# ultrasonic_distance_meter.net
KiCad netlist of a schematic drawn in EAGLE
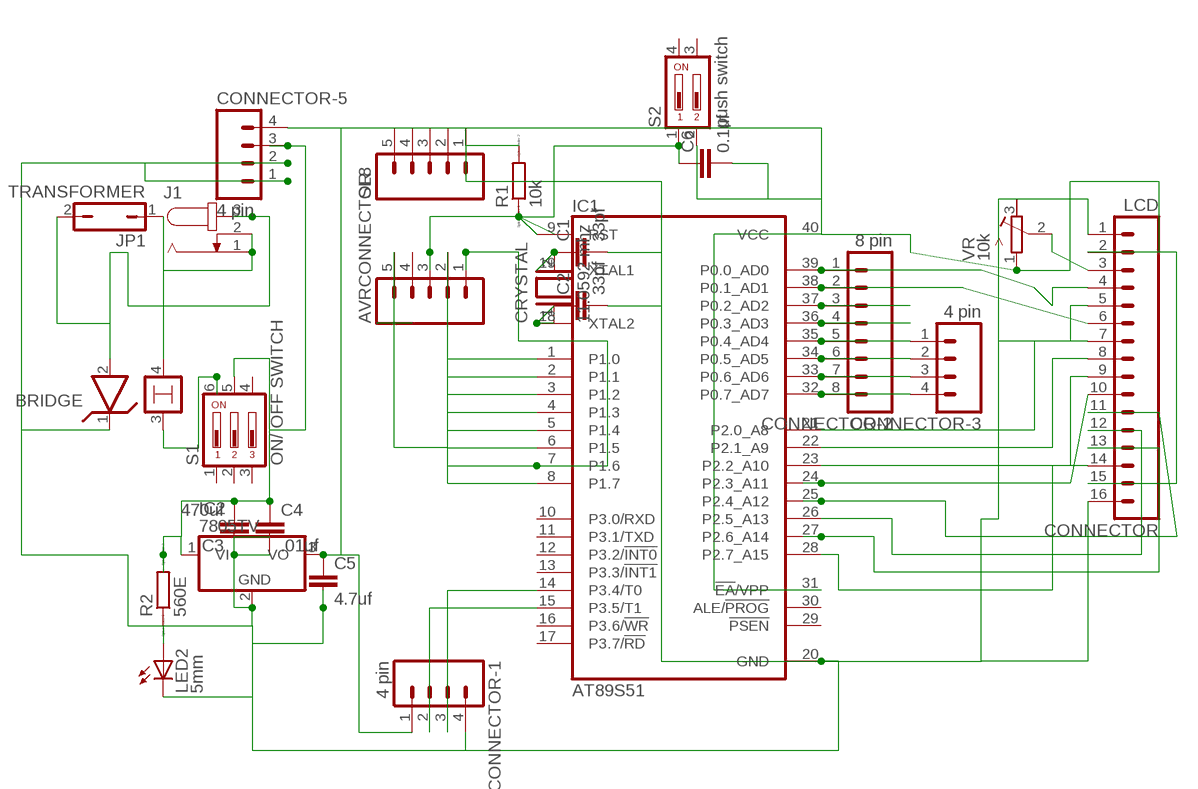
[diagram p0: schematic, sheet 1]

(export (version "E")
  (design (tool "Eeschema 10.0.6"))
  (components
    (comp (ref "AVRCONNECTOR")
      (value "M05")
      (footprint "eagle-import:05P")
      (libsource (lib "eagle-import") (part "M05"))
    )
    (comp (ref "BRIDGE")
      (value "LM399H")
      (footprint "eagle-import:TO39_4")
      (libsource (lib "eagle-import") (part "LM399H"))
    )
    (comp (ref "C1")
      (value "33pf")
      (footprint "eagle-import:C025-024X044")
      (libsource (lib "eagle-import") (part "C-EU025-024X044"))
    )
    (comp (ref "C2")
      (value "33pf")
      (footprint "eagle-import:C025-024X044")
      (libsource (lib "eagle-import") (part "C-EU025-024X044"))
    )
    (comp (ref "C3")
      (value "470uf")
      (footprint "eagle-import:C5B7.2")
      (libsource (lib "eagle-import") (part "C5/7.2"))
    )
    (comp (ref "C4")
      (value ".01uf")
      (footprint "eagle-import:C2.5-3")
      (libsource (lib "eagle-import") (part "C2,5-3"))
    )
    (comp (ref "C5")
      (value "4.7uf")
      (footprint "eagle-import:C2.5-3")
      (libsource (lib "eagle-import") (part "C2,5-3"))
    )
    (comp (ref "C6")
      (value "0.1uf")
      (footprint "eagle-import:C2.5-6")
      (libsource (lib "eagle-import") (part "C2.5/6"))
    )
    (comp (ref "CONNECTOR")
      (value "LCD")
      (footprint "eagle-import:16P")
      (libsource (lib "eagle-import") (part "M16"))
    )
    (comp (ref "CONNECTOR-1")
      (value "4 pin")
      (footprint "eagle-import:04P")
      (fields (field (name "OC_FARNELL") "unknown") (field (name "OC_NEWARK") "unknown"))
      (libsource (lib "eagle-import") (part "M04"))
    )
    (comp (ref "CONNECTOR-2")
      (value "8 pin")
      (footprint "eagle-import:08P")
      (libsource (lib "eagle-import") (part "M08"))
    )
    (comp (ref "CONNECTOR-3")
      (value "4 pin")
      (footprint "eagle-import:04P")
      (fields (field (name "OC_FARNELL") "unknown") (field (name "OC_NEWARK") "unknown"))
      (libsource (lib "eagle-import") (part "M04"))
    )
    (comp (ref "CONNECTOR-5")
      (value "4 pin")
      (footprint "eagle-import:04P")
      (libsource (lib "eagle-import") (part "M04"))
    )
    (comp (ref "CRYSTAL")
      (value "11.0592 mhz")
      (footprint "eagle-import:QS")
      (libsource (lib "eagle-import") (part "XTAL/S"))
    )
    (comp (ref "IC1")
      (value "AT89S51")
      (footprint "eagle-import:DIL40")
      (libsource (lib "eagle-import") (part "AT89C51-PC12"))
    )
    (comp (ref "IC2")
      (value "7805TV")
      (footprint "eagle-import:TO220V")
      (libsource (lib "eagle-import") (part "78TV05"))
    )
    (comp (ref "J1")
      (value "JACK-PLUG0")
      (footprint "eagle-import:SPC4077")
      (libsource (lib "eagle-import") (part "JACK-PLUG0"))
    )
    (comp (ref "JP1")
      (value "TRANSFORMER")
      (footprint "eagle-import:JP1")
      (libsource (lib "eagle-import") (part "JP1Q"))
    )
    (comp (ref "LED2")
      (value "5mm")
      (footprint "eagle-import:LED5MM")
      (libsource (lib "eagle-import") (part "LED5MM"))
    )
    (comp (ref "R1")
      (value "10k")
      (footprint "eagle-import:0204_7")
      (libsource (lib "eagle-import") (part "R0204/7"))
    )
    (comp (ref "R2")
      (value "560E")
      (footprint "eagle-import:0204_7")
      (libsource (lib "eagle-import") (part "R0204/7"))
    )
    (comp (ref "S1")
      (value "ON/ OFF SWITCH")
      (footprint "eagle-import:DA-03")
      (fields (field (name "MPN") "MCDA03"))
      (libsource (lib "eagle-import") (part "DA03"))
    )
    (comp (ref "S2")
      (value "push switch")
      (footprint "eagle-import:DP-02")
      (fields (field (name "MPN") "MCDP02"))
      (libsource (lib "eagle-import") (part "DP02"))
    )
    (comp (ref "SL8")
      (value "M05")
      (footprint "eagle-import:05P")
      (libsource (lib "eagle-import") (part "M05"))
    )
    (comp (ref "VR")
      (value "10k")
      (footprint "eagle-import:RTRIM64P")
      (libsource (lib "eagle-import") (part "R-TRIMM64P"))
    )
  )
  (nets
    (net (code "1") (name "/N$39") (class "Default")
      (node (ref "C5") (pin "1") (pinfunction "1_1") (pintype "passive"))
      (node (ref "C6") (pin "2") (pinfunction "2_2") (pintype "passive"))
      (node (ref "CONNECTOR") (pin "15") (pinfunction "15_15") (pintype "passive"))
      (node (ref "CONNECTOR") (pin "2") (pinfunction "2_2") (pintype "passive"))
      (node (ref "CONNECTOR-1") (pin "1") (pinfunction "1_1") (pintype "passive"))
      (node (ref "CONNECTOR-5") (pin "4") (pinfunction "4_4") (pintype "passive"))
      (node (ref "IC1") (pin "31") (pinfunction "~{EA}/VPP_31") (pintype "input"))
      (node (ref "IC1") (pin "40") (pinfunction "VCC_40") (pintype "power_in"))
      (node (ref "IC2") (pin "3") (pinfunction "VO_3") (pintype "passive"))
      (node (ref "S2") (pin "2") (pinfunction "2_2") (pintype "passive"))
      (node (ref "VR") (pin "1") (pinfunction "E_1") (pintype "passive"))
    )
    (net (code "2") (name "Net-(BRIDGE-Pad2)") (class "Default")
      (node (ref "BRIDGE") (pin "2") (pinfunction "2_2") (pintype "input"))
      (node (ref "J1") (pin "3") (pinfunction "3_3") (pintype "passive"))
      (node (ref "JP1") (pin "2") (pinfunction "2_2") (pintype "passive"))
    )
    (net (code "3") (name "Net-(BRIDGE-Pad3)") (class "Default")
      (node (ref "BRIDGE") (pin "3") (pinfunction "3_3") (pintype "input"))
      (node (ref "S1") (pin "6") (pinfunction "6_6") (pintype "passive"))
    )
    (net (code "4") (name "Net-(BRIDGE-Pad4)") (class "Default")
      (node (ref "BRIDGE") (pin "4") (pinfunction "4_4") (pintype "input"))
      (node (ref "J1") (pin "1") (pinfunction "1_1") (pintype "passive"))
      (node (ref "J1") (pin "2") (pinfunction "2_2") (pintype "passive"))
      (node (ref "JP1") (pin "1") (pinfunction "1_1") (pintype "passive"))
    )
    (net (code "5") (name "Net-(IC1-GND)") (class "Default")
      (node (ref "BRIDGE") (pin "1") (pinfunction "1_1") (pintype "input"))
      (node (ref "C1") (pin "2") (pinfunction "2_2") (pintype "passive"))
      (node (ref "C2") (pin "2") (pinfunction "2_2") (pintype "passive"))
      (node (ref "C3") (pin "1") (pinfunction "1_1") (pintype "passive"))
      (node (ref "C4") (pin "2") (pinfunction "2_2") (pintype "passive"))
      (node (ref "C5") (pin "2") (pinfunction "2_2") (pintype "passive"))
      (node (ref "CONNECTOR") (pin "1") (pinfunction "1_1") (pintype "passive"))
      (node (ref "CONNECTOR") (pin "16") (pinfunction "16_16") (pintype "passive"))
      (node (ref "CONNECTOR") (pin "5") (pinfunction "5_5") (pintype "passive"))
      (node (ref "CONNECTOR-1") (pin "4") (pinfunction "4_4") (pintype "passive"))
      (node (ref "CONNECTOR-5") (pin "1") (pinfunction "1_1") (pintype "passive"))
      (node (ref "CONNECTOR-5") (pin "2") (pinfunction "2_2") (pintype "passive"))
      (node (ref "IC1") (pin "20") (pinfunction "GND_20") (pintype "power_in"))
      (node (ref "IC2") (pin "2") (pinfunction "GND_2") (pintype "passive"))
      (node (ref "LED2") (pin "K") (pinfunction "C_K") (pintype "passive"))
      (node (ref "R1") (pin "2") (pinfunction "2_2") (pintype "passive"))
      (node (ref "SL8") (pin "1") (pinfunction "1_1") (pintype "passive"))
      (node (ref "VR") (pin "3") (pinfunction "A_3") (pintype "passive"))
    )
    (net (code "6") (name "Net-(IC1-P0.0_AD0)") (class "Default")
      (node (ref "CONNECTOR") (pin "4") (pinfunction "4_4") (pintype "passive"))
      (node (ref "CONNECTOR-2") (pin "1") (pinfunction "1_1") (pintype "passive"))
      (node (ref "IC1") (pin "39") (pinfunction "P0.0_AD0_39") (pintype "bidirectional"))
    )
    (net (code "7") (name "Net-(IC1-P0.1_AD1)") (class "Default")
      (node (ref "CONNECTOR") (pin "6") (pinfunction "6_6") (pintype "passive"))
      (node (ref "CONNECTOR-2") (pin "2") (pinfunction "2_2") (pintype "passive"))
      (node (ref "IC1") (pin "38") (pinfunction "P0.1_AD1_38") (pintype "bidirectional"))
    )
    (net (code "8") (name "Net-(IC1-P0.2_AD2)") (class "Default")
      (node (ref "CONNECTOR-2") (pin "3") (pinfunction "3_3") (pintype "passive"))
      (node (ref "IC1") (pin "37") (pinfunction "P0.2_AD2_37") (pintype "bidirectional"))
    )
    (net (code "9") (name "Net-(IC1-P0.3_AD3)") (class "Default")
      (node (ref "CONNECTOR-2") (pin "4") (pinfunction "4_4") (pintype "passive"))
      (node (ref "IC1") (pin "36") (pinfunction "P0.3_AD3_36") (pintype "bidirectional"))
    )
    (net (code "10") (name "Net-(IC1-P0.4_AD4)") (class "Default")
      (node (ref "CONNECTOR-2") (pin "5") (pinfunction "5_5") (pintype "passive"))
      (node (ref "CONNECTOR-3") (pin "1") (pinfunction "1_1") (pintype "passive"))
      (node (ref "IC1") (pin "35") (pinfunction "P0.4_AD4_35") (pintype "bidirectional"))
    )
    (net (code "11") (name "Net-(IC1-P0.5_AD5)") (class "Default")
      (node (ref "CONNECTOR-2") (pin "6") (pinfunction "6_6") (pintype "passive"))
      (node (ref "CONNECTOR-3") (pin "2") (pinfunction "2_2") (pintype "passive"))
      (node (ref "IC1") (pin "34") (pinfunction "P0.5_AD5_34") (pintype "bidirectional"))
    )
    (net (code "12") (name "Net-(IC1-P0.6_AD6)") (class "Default")
      (node (ref "CONNECTOR-2") (pin "7") (pinfunction "7_7") (pintype "passive"))
      (node (ref "CONNECTOR-3") (pin "3") (pinfunction "3_3") (pintype "passive"))
      (node (ref "IC1") (pin "33") (pinfunction "P0.6_AD6_33") (pintype "bidirectional"))
    )
    (net (code "13") (name "Net-(IC1-P0.7_AD7)") (class "Default")
      (node (ref "CONNECTOR-2") (pin "8") (pinfunction "8_8") (pintype "passive"))
      (node (ref "CONNECTOR-3") (pin "4") (pinfunction "4_4") (pintype "passive"))
      (node (ref "IC1") (pin "32") (pinfunction "P0.7_AD7_32") (pintype "bidirectional"))
    )
    (net (code "14") (name "Net-(IC1-P1.5)") (class "Default")
      (node (ref "AVRCONNECTOR") (pin "5") (pinfunction "5_5") (pintype "passive"))
      (node (ref "IC1") (pin "6") (pinfunction "P1.5_6") (pintype "bidirectional"))
    )
    (net (code "15") (name "Net-(IC1-P1.6)") (class "Default")
      (node (ref "AVRCONNECTOR") (pin "1") (pinfunction "1_1") (pintype "passive"))
      (node (ref "IC1") (pin "7") (pinfunction "P1.6_7") (pintype "bidirectional"))
    )
    (net (code "16") (name "Net-(IC1-P1.7)") (class "Default")
      (node (ref "AVRCONNECTOR") (pin "2") (pinfunction "2_2") (pintype "passive"))
      (node (ref "IC1") (pin "8") (pinfunction "P1.7_8") (pintype "bidirectional"))
    )
    (net (code "17") (name "Net-(IC1-P2.0_A8)") (class "Default")
      (node (ref "CONNECTOR") (pin "7") (pinfunction "7_7") (pintype "passive"))
      (node (ref "IC1") (pin "21") (pinfunction "P2.0_A8_21") (pintype "bidirectional"))
    )
    (net (code "18") (name "Net-(IC1-P2.1_A9)") (class "Default")
      (node (ref "CONNECTOR") (pin "8") (pinfunction "8_8") (pintype "passive"))
      (node (ref "IC1") (pin "22") (pinfunction "P2.1_A9_22") (pintype "bidirectional"))
    )
    (net (code "19") (name "Net-(IC1-P2.2_A10)") (class "Default")
      (node (ref "CONNECTOR") (pin "9") (pinfunction "9_9") (pintype "passive"))
      (node (ref "IC1") (pin "23") (pinfunction "P2.2_A10_23") (pintype "bidirectional"))
    )
    (net (code "20") (name "Net-(IC1-P2.3_A11)") (class "Default")
      (node (ref "CONNECTOR") (pin "10") (pinfunction "10_10") (pintype "passive"))
      (node (ref "IC1") (pin "24") (pinfunction "P2.3_A11_24") (pintype "bidirectional"))
    )
    (net (code "21") (name "Net-(IC1-P2.4_A12)") (class "Default")
      (node (ref "CONNECTOR") (pin "11") (pinfunction "11_11") (pintype "passive"))
      (node (ref "IC1") (pin "25") (pinfunction "P2.4_A12_25") (pintype "bidirectional"))
    )
    (net (code "22") (name "Net-(IC1-P2.5_A13)") (class "Default")
      (node (ref "CONNECTOR") (pin "12") (pinfunction "12_12") (pintype "passive"))
      (node (ref "IC1") (pin "26") (pinfunction "P2.5_A13_26") (pintype "bidirectional"))
    )
    (net (code "23") (name "Net-(IC1-P2.6_A14)") (class "Default")
      (node (ref "CONNECTOR") (pin "13") (pinfunction "13_13") (pintype "passive"))
      (node (ref "IC1") (pin "27") (pinfunction "P2.6_A14_27") (pintype "bidirectional"))
    )
    (net (code "24") (name "Net-(IC1-P2.7_A15)") (class "Default")
      (node (ref "CONNECTOR") (pin "14") (pinfunction "14_14") (pintype "passive"))
      (node (ref "IC1") (pin "28") (pinfunction "P2.7_A15_28") (pintype "bidirectional"))
    )
    (net (code "25") (name "Net-(IC1-P3.4{slash}T0)") (class "Default")
      (node (ref "CONNECTOR-1") (pin "3") (pinfunction "3_3") (pintype "passive"))
      (node (ref "IC1") (pin "14") (pinfunction "P3.4/T0_14") (pintype "bidirectional"))
    )
    (net (code "26") (name "Net-(IC1-P3.5{slash}T1)") (class "Default")
      (node (ref "CONNECTOR-1") (pin "2") (pinfunction "2_2") (pintype "passive"))
      (node (ref "IC1") (pin "15") (pinfunction "P3.5/T1_15") (pintype "bidirectional"))
    )
    (net (code "27") (name "Net-(IC1-RST)") (class "Default")
      (node (ref "AVRCONNECTOR") (pin "3") (pinfunction "3_3") (pintype "passive"))
      (node (ref "C6") (pin "1") (pinfunction "1_1") (pintype "passive"))
      (node (ref "IC1") (pin "9") (pinfunction "RST_9") (pintype "input"))
      (node (ref "R1") (pin "1") (pinfunction "1_1") (pintype "passive"))
      (node (ref "S2") (pin "1") (pinfunction "1_1") (pintype "passive"))
    )
    (net (code "28") (name "Net-(IC1-XTAL1)") (class "Default")
      (node (ref "C1") (pin "1") (pinfunction "1_1") (pintype "passive"))
      (node (ref "CRYSTAL") (pin "2") (pinfunction "2_2") (pintype "passive"))
      (node (ref "IC1") (pin "19") (pinfunction "XTAL1_19") (pintype "input"))
    )
    (net (code "29") (name "Net-(IC1-XTAL2)") (class "Default")
      (node (ref "C2") (pin "1") (pinfunction "1_1") (pintype "passive"))
      (node (ref "CRYSTAL") (pin "1") (pinfunction "1_1") (pintype "passive"))
      (node (ref "IC1") (pin "18") (pinfunction "XTAL2_18") (pintype "input"))
    )
    (net (code "30") (name "Net-(IC2-VI)") (class "Default")
      (node (ref "C3") (pin "2") (pinfunction "2_2") (pintype "passive"))
      (node (ref "C4") (pin "1") (pinfunction "1_1") (pintype "passive"))
      (node (ref "CONNECTOR-5") (pin "3") (pinfunction "3_3") (pintype "passive"))
      (node (ref "IC2") (pin "1") (pinfunction "VI_1") (pintype "input"))
      (node (ref "R2") (pin "2") (pinfunction "2_2") (pintype "passive"))
      (node (ref "S1") (pin "5") (pinfunction "5_5") (pintype "passive"))
    )
    (net (code "31") (name "Net-(LED2-PadA)") (class "Default")
      (node (ref "LED2") (pin "A") (pinfunction "A_A") (pintype "passive"))
      (node (ref "R2") (pin "1") (pinfunction "1_1") (pintype "passive"))
    )
    (net (code "32") (name "Net-(VR-S)") (class "Default")
      (node (ref "CONNECTOR") (pin "3") (pinfunction "3_3") (pintype "passive"))
      (node (ref "VR") (pin "2") (pinfunction "S_2") (pintype "passive"))
    )
    (net (code "33") (name "unconnected-(AVRCONNECTOR-Pad4)") (class "Default")
      (node (ref "AVRCONNECTOR") (pin "4") (pinfunction "4_4") (pintype "passive"))
    )
    (net (code "34") (name "unconnected-(IC1-ALE{slash}~{PROG}-Pad30)") (class "Default")
      (node (ref "IC1") (pin "30") (pinfunction "ALE/~{PROG}_30") (pintype "output"))
    )
    (net (code "35") (name "unconnected-(IC1-P1.0-Pad1)") (class "Default")
      (node (ref "IC1") (pin "1") (pinfunction "P1.0_1") (pintype "bidirectional"))
    )
    (net (code "36") (name "unconnected-(IC1-P1.1-Pad2)") (class "Default")
      (node (ref "IC1") (pin "2") (pinfunction "P1.1_2") (pintype "bidirectional"))
    )
    (net (code "37") (name "unconnected-(IC1-P1.2-Pad3)") (class "Default")
      (node (ref "IC1") (pin "3") (pinfunction "P1.2_3") (pintype "bidirectional"))
    )
    (net (code "38") (name "unconnected-(IC1-P1.3-Pad4)") (class "Default")
      (node (ref "IC1") (pin "4") (pinfunction "P1.3_4") (pintype "bidirectional"))
    )
    (net (code "39") (name "unconnected-(IC1-P1.4-Pad5)") (class "Default")
      (node (ref "IC1") (pin "5") (pinfunction "P1.4_5") (pintype "bidirectional"))
    )
    (net (code "40") (name "unconnected-(IC1-P3.0{slash}RXD-Pad10)") (class "Default")
      (node (ref "IC1") (pin "10") (pinfunction "P3.0/RXD_10") (pintype "bidirectional"))
    )
    (net (code "41") (name "unconnected-(IC1-P3.1{slash}TXD-Pad11)") (class "Default")
      (node (ref "IC1") (pin "11") (pinfunction "P3.1/TXD_11") (pintype "bidirectional"))
    )
    (net (code "42") (name "unconnected-(IC1-P3.2{slash}~{INT0}-Pad12)") (class "Default")
      (node (ref "IC1") (pin "12") (pinfunction "P3.2/~{INT0}_12") (pintype "bidirectional"))
    )
    (net (code "43") (name "unconnected-(IC1-P3.3{slash}~{INT1}-Pad13)") (class "Default")
      (node (ref "IC1") (pin "13") (pinfunction "P3.3/~{INT1}_13") (pintype "bidirectional"))
    )
    (net (code "44") (name "unconnected-(IC1-P3.6{slash}~{WR}-Pad16)") (class "Default")
      (node (ref "IC1") (pin "16") (pinfunction "P3.6/~{WR}_16") (pintype "bidirectional"))
    )
    (net (code "45") (name "unconnected-(IC1-P3.7{slash}~{RD}-Pad17)") (class "Default")
      (node (ref "IC1") (pin "17") (pinfunction "P3.7/~{RD}_17") (pintype "bidirectional"))
    )
    (net (code "46") (name "unconnected-(IC1-~{PSEN}-Pad29)") (class "Default")
      (node (ref "IC1") (pin "29") (pinfunction "~{PSEN}_29") (pintype "output"))
    )
    (net (code "47") (name "unconnected-(S1-Pad1)") (class "Default")
      (node (ref "S1") (pin "1") (pinfunction "1_1") (pintype "passive"))
    )
    (net (code "48") (name "unconnected-(S1-Pad2)") (class "Default")
      (node (ref "S1") (pin "2") (pinfunction "2_2") (pintype "passive"))
    )
    (net (code "49") (name "unconnected-(S1-Pad3)") (class "Default")
      (node (ref "S1") (pin "3") (pinfunction "3_3") (pintype "passive"))
    )
    (net (code "50") (name "unconnected-(S1-Pad4)") (class "Default")
      (node (ref "S1") (pin "4") (pinfunction "4_4") (pintype "passive"))
    )
    (net (code "51") (name "unconnected-(S2-Pad3)") (class "Default")
      (node (ref "S2") (pin "3") (pinfunction "3_3") (pintype "passive"))
    )
    (net (code "52") (name "unconnected-(S2-Pad4)") (class "Default")
      (node (ref "S2") (pin "4") (pinfunction "4_4") (pintype "passive"))
    )
    (net (code "53") (name "unconnected-(SL8-Pad2)") (class "Default")
      (node (ref "SL8") (pin "2") (pinfunction "2_2") (pintype "passive"))
    )
    (net (code "54") (name "unconnected-(SL8-Pad3)") (class "Default")
      (node (ref "SL8") (pin "3") (pinfunction "3_3") (pintype "passive"))
    )
    (net (code "55") (name "unconnected-(SL8-Pad4)") (class "Default")
      (node (ref "SL8") (pin "4") (pinfunction "4_4") (pintype "passive"))
    )
    (net (code "56") (name "unconnected-(SL8-Pad5)") (class "Default")
      (node (ref "SL8") (pin "5") (pinfunction "5_5") (pintype "passive"))
    )
  )
)
